# Top.net
KiCad netlist of a schematic drawn in Altium Designer
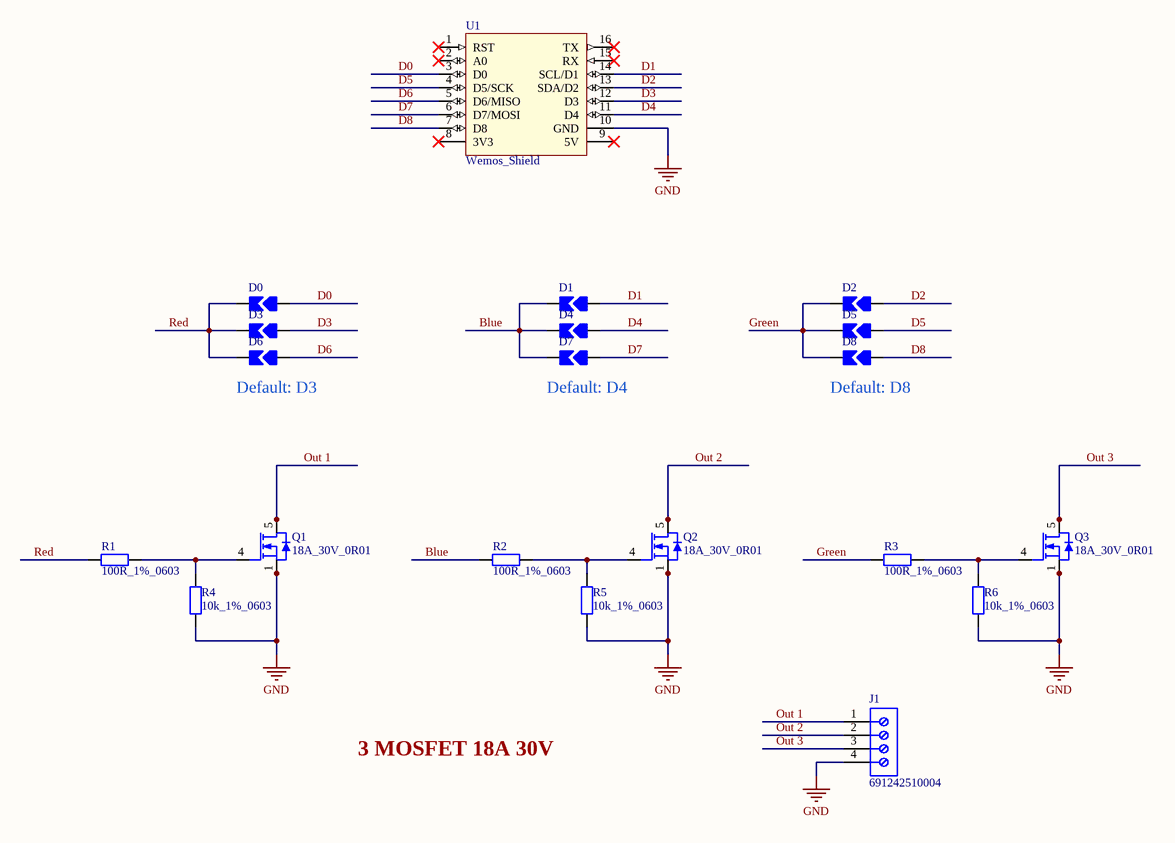
[diagram p0: Top.SchDoc]

(export (version "E")
  (design (tool "Eeschema 10.0.6"))
  (components
    (comp (ref "D0")
      (value "SWITCH_SOUDABLE")
      (footprint "Switch_Soudable")
      (libsource (lib "Common") (part "SWITCH_SOUDABLE"))
    )
    (comp (ref "D1")
      (value "SWITCH_SOUDABLE")
      (footprint "Switch_Soudable")
      (libsource (lib "Common") (part "SWITCH_SOUDABLE"))
    )
    (comp (ref "D2")
      (value "SWITCH_SOUDABLE")
      (footprint "Switch_Soudable")
      (libsource (lib "Common") (part "SWITCH_SOUDABLE"))
    )
    (comp (ref "D3")
      (value "SWITCH_SOUDABLE")
      (footprint "Switch_Soudable")
      (libsource (lib "Common") (part "SWITCH_SOUDABLE"))
    )
    (comp (ref "D4")
      (value "SWITCH_SOUDABLE")
      (footprint "Switch_Soudable")
      (libsource (lib "Common") (part "SWITCH_SOUDABLE"))
    )
    (comp (ref "D5")
      (value "SWITCH_SOUDABLE")
      (footprint "Switch_Soudable")
      (libsource (lib "Common") (part "SWITCH_SOUDABLE"))
    )
    (comp (ref "D6")
      (value "SWITCH_SOUDABLE")
      (footprint "Switch_Soudable")
      (libsource (lib "Common") (part "SWITCH_SOUDABLE"))
    )
    (comp (ref "D7")
      (value "SWITCH_SOUDABLE")
      (footprint "Switch_Soudable")
      (libsource (lib "Common") (part "SWITCH_SOUDABLE"))
    )
    (comp (ref "D8")
      (value "SWITCH_SOUDABLE")
      (footprint "Switch_Soudable")
      (libsource (lib "Common") (part "SWITCH_SOUDABLE"))
    )
    (comp (ref "J1")
      (value "691242510004")
      (footprint "691242510004")
      (description "WR-TBL Serie 2425 Horizontal Entry Modular, Rising Cage Clamp, pitch 5.08mm, 4p")
      (fields (field (name "PUBLISHER") "Wurth Elektronik"))
      (libsource (lib "WR-TBL_rev19a") (part "691242510004"))
    )
    (comp (ref "Q1")
      (value "18A_30V_0R01")
      (footprint "PQFN8_3.3x3.3")
      (description "N-Channel MOSFET")
      (fields (field (name "MF") "INFINEON") (field (name "MPN") "IRFHM8337"))
      (libsource (lib "Common") (part "MOSFET-N"))
    )
    (comp (ref "Q2")
      (value "18A_30V_0R01")
      (footprint "PQFN8_3.3x3.3")
      (description "N-Channel MOSFET")
      (fields (field (name "MF") "INFINEON") (field (name "MPN") "IRFHM8337"))
      (libsource (lib "Common") (part "MOSFET-N"))
    )
    (comp (ref "Q3")
      (value "18A_30V_0R01")
      (footprint "PQFN8_3.3x3.3")
      (description "N-Channel MOSFET")
      (fields (field (name "MF") "INFINEON") (field (name "MPN") "IRFHM8337"))
      (libsource (lib "Common") (part "MOSFET-N"))
    )
    (comp (ref "R1")
      (value "100R_1%_0603")
      (footprint "R0603")
      (description "Resistor")
      (fields (field (name "MPN") "MCWR06X1000FTL") (field (name "MF") "MULTICOMP"))
      (libsource (lib "Common") (part "RES"))
    )
    (comp (ref "R2")
      (value "100R_1%_0603")
      (footprint "R0603")
      (description "Resistor")
      (fields (field (name "MPN") "MCWR06X1000FTL") (field (name "MF") "MULTICOMP"))
      (libsource (lib "Common") (part "RES"))
    )
    (comp (ref "R3")
      (value "100R_1%_0603")
      (footprint "R0603")
      (description "Resistor")
      (fields (field (name "MPN") "MCWR06X1000FTL") (field (name "MF") "MULTICOMP"))
      (libsource (lib "Common") (part "RES"))
    )
    (comp (ref "R4")
      (value "10k_1%_0603")
      (footprint "R0603")
      (description "Resistor")
      (fields (field (name "MPN") "MCWR06X1002FTL") (field (name "MF") "MULTICOMP"))
      (libsource (lib "") (part "RES_1"))
    )
    (comp (ref "R5")
      (value "10k_1%_0603")
      (footprint "R0603")
      (description "Resistor")
      (fields (field (name "MPN") "MCWR06X1002FTL") (field (name "MF") "MULTICOMP"))
      (libsource (lib "") (part "RES_1"))
    )
    (comp (ref "R6")
      (value "10k_1%_0603")
      (footprint "R0603")
      (description "Resistor")
      (fields (field (name "MPN") "MCWR06X1002FTL") (field (name "MF") "MULTICOMP"))
      (libsource (lib "") (part "RES_1"))
    )
    (comp (ref "U1")
      (value "Wemos_Shield")
      (footprint "WEMOS_D1_MINI")
      (libsource (lib "Common") (part "ESP8266"))
    )
  )
  (nets
    (net (code "1") (name "/Blue") (class "Default")
      (node (ref "D1") (pin "0") (pinfunction "0_0") (pintype "passive"))
      (node (ref "D4") (pin "0") (pinfunction "0_0") (pintype "passive"))
      (node (ref "D7") (pin "0") (pinfunction "0_0") (pintype "passive"))
      (node (ref "R2") (pin "2") (pinfunction "2_2") (pintype "passive"))
    )
    (net (code "2") (name "/D0") (class "Default")
      (node (ref "D0") (pin "1") (pinfunction "1_1") (pintype "passive"))
      (node (ref "U1") (pin "3") (pinfunction "D0_3") (pintype "bidirectional"))
    )
    (net (code "3") (name "/D1") (class "Default")
      (node (ref "D1") (pin "1") (pinfunction "1_1") (pintype "passive"))
      (node (ref "U1") (pin "14") (pinfunction "SCL/D1_14") (pintype "bidirectional"))
    )
    (net (code "4") (name "/D2") (class "Default")
      (node (ref "D2") (pin "1") (pinfunction "1_1") (pintype "passive"))
      (node (ref "U1") (pin "13") (pinfunction "SDA/D2_13") (pintype "bidirectional"))
    )
    (net (code "5") (name "/D3") (class "Default")
      (node (ref "D3") (pin "1") (pinfunction "1_1") (pintype "passive"))
      (node (ref "U1") (pin "12") (pinfunction "D3_12") (pintype "bidirectional"))
    )
    (net (code "6") (name "/D4") (class "Default")
      (node (ref "D4") (pin "1") (pinfunction "1_1") (pintype "passive"))
      (node (ref "U1") (pin "11") (pinfunction "D4_11") (pintype "bidirectional"))
    )
    (net (code "7") (name "/D5") (class "Default")
      (node (ref "D5") (pin "1") (pinfunction "1_1") (pintype "passive"))
      (node (ref "U1") (pin "4") (pinfunction "D5/SCK_4") (pintype "bidirectional"))
    )
    (net (code "8") (name "/D6") (class "Default")
      (node (ref "D6") (pin "1") (pinfunction "1_1") (pintype "passive"))
      (node (ref "U1") (pin "5") (pinfunction "D6/MISO_5") (pintype "bidirectional"))
    )
    (net (code "9") (name "/D7") (class "Default")
      (node (ref "D7") (pin "1") (pinfunction "1_1") (pintype "passive"))
      (node (ref "U1") (pin "6") (pinfunction "D7/MOSI_6") (pintype "bidirectional"))
    )
    (net (code "10") (name "/D8") (class "Default")
      (node (ref "D8") (pin "1") (pinfunction "1_1") (pintype "passive"))
      (node (ref "U1") (pin "7") (pinfunction "D8_7") (pintype "bidirectional"))
    )
    (net (code "11") (name "/Green") (class "Default")
      (node (ref "D2") (pin "0") (pinfunction "0_0") (pintype "passive"))
      (node (ref "D5") (pin "0") (pinfunction "0_0") (pintype "passive"))
      (node (ref "D8") (pin "0") (pinfunction "0_0") (pintype "passive"))
      (node (ref "R3") (pin "2") (pinfunction "2_2") (pintype "passive"))
    )
    (net (code "12") (name "/Out 1") (class "Default")
      (node (ref "J1") (pin "1") (pinfunction "1_1") (pintype "passive"))
      (node (ref "Q1") (pin "5") (pinfunction "D_5") (pintype "passive"))
      (node (ref "Q1") (pin "6") (pinfunction "D_6") (pintype "power_in"))
      (node (ref "Q1") (pin "7") (pinfunction "D_7") (pintype "power_in"))
      (node (ref "Q1") (pin "8") (pinfunction "D_8") (pintype "power_in"))
    )
    (net (code "13") (name "/Out 2") (class "Default")
      (node (ref "J1") (pin "2") (pinfunction "2_2") (pintype "passive"))
      (node (ref "Q2") (pin "5") (pinfunction "D_5") (pintype "passive"))
      (node (ref "Q2") (pin "6") (pinfunction "D_6") (pintype "power_in"))
      (node (ref "Q2") (pin "7") (pinfunction "D_7") (pintype "power_in"))
      (node (ref "Q2") (pin "8") (pinfunction "D_8") (pintype "power_in"))
    )
    (net (code "14") (name "/Out 3") (class "Default")
      (node (ref "J1") (pin "3") (pinfunction "3_3") (pintype "passive"))
      (node (ref "Q3") (pin "5") (pinfunction "D_5") (pintype "passive"))
      (node (ref "Q3") (pin "6") (pinfunction "D_6") (pintype "power_in"))
      (node (ref "Q3") (pin "7") (pinfunction "D_7") (pintype "power_in"))
      (node (ref "Q3") (pin "8") (pinfunction "D_8") (pintype "power_in"))
    )
    (net (code "15") (name "/Red") (class "Default")
      (node (ref "D0") (pin "0") (pinfunction "0_0") (pintype "passive"))
      (node (ref "D3") (pin "0") (pinfunction "0_0") (pintype "passive"))
      (node (ref "D6") (pin "0") (pinfunction "0_0") (pintype "passive"))
      (node (ref "R1") (pin "2") (pinfunction "2_2") (pintype "passive"))
    )
    (net (code "16") (name "GND") (class "Default")
      (node (ref "J1") (pin "4") (pinfunction "4_4") (pintype "passive"))
      (node (ref "Q1") (pin "1") (pinfunction "S_1") (pintype "passive"))
      (node (ref "Q1") (pin "2") (pinfunction "S_2") (pintype "power_in"))
      (node (ref "Q1") (pin "3") (pinfunction "S_3") (pintype "power_in"))
      (node (ref "Q2") (pin "1") (pinfunction "S_1") (pintype "passive"))
      (node (ref "Q2") (pin "2") (pinfunction "S_2") (pintype "power_in"))
      (node (ref "Q2") (pin "3") (pinfunction "S_3") (pintype "power_in"))
      (node (ref "Q3") (pin "1") (pinfunction "S_1") (pintype "passive"))
      (node (ref "Q3") (pin "2") (pinfunction "S_2") (pintype "power_in"))
      (node (ref "Q3") (pin "3") (pinfunction "S_3") (pintype "power_in"))
      (node (ref "R4") (pin "1") (pinfunction "1_1") (pintype "passive"))
      (node (ref "R5") (pin "1") (pinfunction "1_1") (pintype "passive"))
      (node (ref "R6") (pin "1") (pinfunction "1_1") (pintype "passive"))
      (node (ref "U1") (pin "10") (pinfunction "GND_10") (pintype "power_in"))
    )
    (net (code "17") (name "Net-(Q1-G)") (class "Default")
      (node (ref "Q1") (pin "4") (pinfunction "G_4") (pintype "passive"))
      (node (ref "R1") (pin "1") (pinfunction "1_1") (pintype "passive"))
      (node (ref "R4") (pin "2") (pinfunction "2_2") (pintype "passive"))
    )
    (net (code "18") (name "Net-(Q2-G)") (class "Default")
      (node (ref "Q2") (pin "4") (pinfunction "G_4") (pintype "passive"))
      (node (ref "R2") (pin "1") (pinfunction "1_1") (pintype "passive"))
      (node (ref "R5") (pin "2") (pinfunction "2_2") (pintype "passive"))
    )
    (net (code "19") (name "Net-(Q3-G)") (class "Default")
      (node (ref "Q3") (pin "4") (pinfunction "G_4") (pintype "passive"))
      (node (ref "R3") (pin "1") (pinfunction "1_1") (pintype "passive"))
      (node (ref "R6") (pin "2") (pinfunction "2_2") (pintype "passive"))
    )
    (net (code "20") (name "unconnected-(U1-3V3-Pad8)") (class "Default")
      (node (ref "U1") (pin "8") (pinfunction "3V3_8") (pintype "power_in+no_connect"))
    )
    (net (code "21") (name "unconnected-(U1-5V-Pad9)") (class "Default")
      (node (ref "U1") (pin "9") (pinfunction "5V_9") (pintype "power_in+no_connect"))
    )
    (net (code "22") (name "unconnected-(U1-A0-Pad2)") (class "Default")
      (node (ref "U1") (pin "2") (pinfunction "A0_2") (pintype "bidirectional+no_connect"))
    )
    (net (code "23") (name "unconnected-(U1-RST-Pad1)") (class "Default")
      (node (ref "U1") (pin "1") (pinfunction "RST_1") (pintype "input+no_connect"))
    )
    (net (code "24") (name "unconnected-(U1-RX-Pad15)") (class "Default")
      (node (ref "U1") (pin "15") (pinfunction "RX_15") (pintype "input+no_connect"))
    )
    (net (code "25") (name "unconnected-(U1-TX-Pad16)") (class "Default")
      (node (ref "U1") (pin "16") (pinfunction "TX_16") (pintype "output+no_connect"))
    )
  )
)
